# 130809_AriloTX_0_0.net
KiCad netlist of a schematic drawn in EAGLE
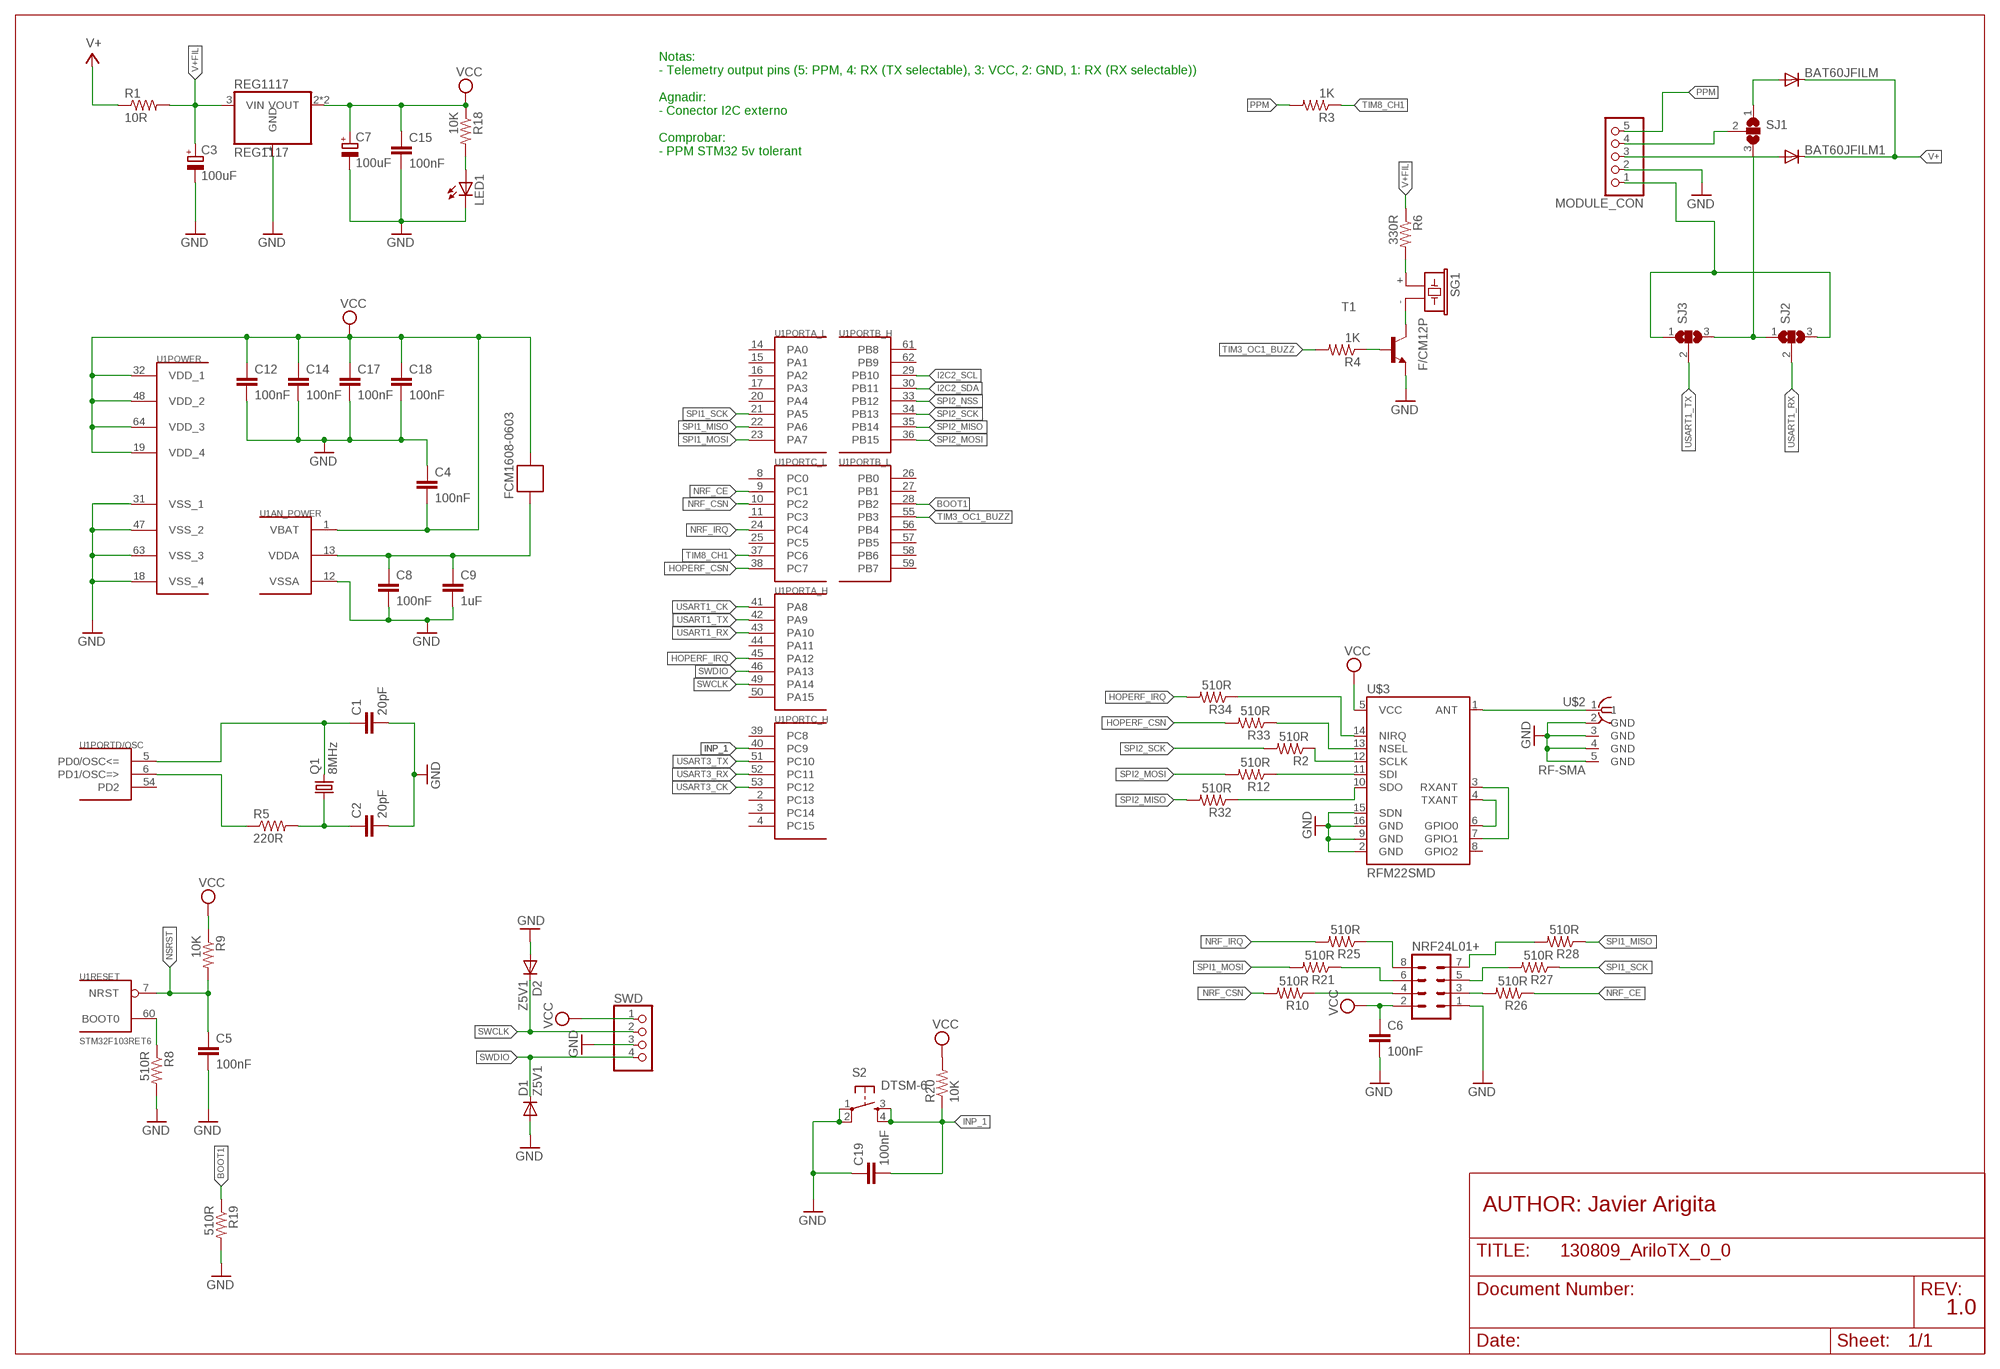
[diagram p0: schematic, sheet 1]

(export (version "E")
  (design (tool "Eeschema 10.0.6"))
  (components
    (comp (ref "BAT60JFILM")
      (value "DIODE-SOD323-R")
      (footprint "eagle-import:SOD323-R")
      (libsource (lib "eagle-import") (part "DIODE-SOD323-R"))
    )
    (comp (ref "BAT60JFILM1")
      (value "DIODE-SOD323-R")
      (footprint "eagle-import:SOD323-R")
      (libsource (lib "eagle-import") (part "DIODE-SOD323-R"))
    )
    (comp (ref "C1")
      (value "20pF")
      (footprint "eagle-import:C0805")
      (libsource (lib "eagle-import") (part "C-EUC0805"))
    )
    (comp (ref "C2")
      (value "20pF")
      (footprint "eagle-import:C0805")
      (libsource (lib "eagle-import") (part "C-EUC0805"))
    )
    (comp (ref "C3")
      (value "100uF")
      (footprint "eagle-import:SMC_B")
      (libsource (lib "eagle-import") (part "CPOL-EUSMCB"))
    )
    (comp (ref "C4")
      (value "100nF")
      (footprint "eagle-import:C0805")
      (libsource (lib "eagle-import") (part "C-EUC0805"))
    )
    (comp (ref "C5")
      (value "100nF")
      (footprint "eagle-import:C0805")
      (libsource (lib "eagle-import") (part "C-EUC0805"))
    )
    (comp (ref "C6")
      (value "100nF")
      (footprint "eagle-import:C0805")
      (libsource (lib "eagle-import") (part "C-EUC0805"))
    )
    (comp (ref "C7")
      (value "100uF")
      (footprint "eagle-import:SMC_B")
      (libsource (lib "eagle-import") (part "CPOL-EUSMCB"))
    )
    (comp (ref "C8")
      (value "100nF")
      (footprint "eagle-import:C0805")
      (libsource (lib "eagle-import") (part "C-EUC0805"))
    )
    (comp (ref "C9")
      (value "1uF")
      (footprint "eagle-import:C3216")
      (libsource (lib "eagle-import") (part "resistor_C-EUC3216"))
    )
    (comp (ref "C12")
      (value "100nF")
      (footprint "eagle-import:C0805")
      (libsource (lib "eagle-import") (part "C-EUC0805"))
    )
    (comp (ref "C14")
      (value "100nF")
      (footprint "eagle-import:C0805")
      (libsource (lib "eagle-import") (part "C-EUC0805"))
    )
    (comp (ref "C15")
      (value "100nF")
      (footprint "eagle-import:C0805")
      (libsource (lib "eagle-import") (part "C-EUC0805"))
    )
    (comp (ref "C17")
      (value "100nF")
      (footprint "eagle-import:C0805")
      (libsource (lib "eagle-import") (part "C-EUC0805"))
    )
    (comp (ref "C18")
      (value "100nF")
      (footprint "eagle-import:C0805")
      (libsource (lib "eagle-import") (part "C-EUC0805"))
    )
    (comp (ref "C19")
      (value "100nF")
      (footprint "eagle-import:C0805")
      (libsource (lib "eagle-import") (part "C-EUC0805"))
    )
    (comp (ref "D1")
      (value "Z5V1")
      (footprint "eagle-import:SOD323-R")
      (libsource (lib "eagle-import") (part "DIODE-SOD323-R"))
    )
    (comp (ref "D2")
      (value "Z5V1")
      (footprint "eagle-import:SOD323-R")
      (libsource (lib "eagle-import") (part "DIODE-SOD323-R"))
    )
    (comp (ref "FCM1608-0603")
      (value "FERRITE-BEAD")
      (footprint "eagle-import:R0603")
      (libsource (lib "eagle-import") (part "FERRITE-BEAD"))
    )
    (comp (ref "LED1")
      (value "LED0805")
      (footprint "eagle-import:CHIPLED_0805")
      (libsource (lib "eagle-import") (part "LED0805"))
    )
    (comp (ref "MODULE_CON")
      (value "PINHD-1X5")
      (footprint "eagle-import:1X05")
      (libsource (lib "eagle-import") (part "PINHD-1X5"))
    )
    (comp (ref "NRF24L01+")
      (value "MA04-2")
      (footprint "eagle-import:MA04-2")
      (libsource (lib "eagle-import") (part "MA04-2"))
    )
    (comp (ref "Q1")
      (value "8MHz")
      (footprint "eagle-import:SM49")
      (libsource (lib "eagle-import") (part "CRYSTALSM49"))
    )
    (comp (ref "R1")
      (value "10R")
      (footprint "eagle-import:R0805")
      (libsource (lib "eagle-import") (part "RESISTOR0805"))
    )
    (comp (ref "R2")
      (value "510R")
      (footprint "eagle-import:R0805")
      (libsource (lib "eagle-import") (part "RESISTOR0805"))
    )
    (comp (ref "R3")
      (value "1K")
      (footprint "eagle-import:R0805")
      (libsource (lib "eagle-import") (part "RESISTOR0805"))
    )
    (comp (ref "R4")
      (value "1K")
      (footprint "eagle-import:R0805")
      (libsource (lib "eagle-import") (part "RESISTOR0805"))
    )
    (comp (ref "R5")
      (value "220R")
      (footprint "eagle-import:R0805")
      (libsource (lib "eagle-import") (part "RESISTOR0805"))
    )
    (comp (ref "R6")
      (value "330R")
      (footprint "eagle-import:R0805")
      (libsource (lib "eagle-import") (part "RESISTOR0805"))
    )
    (comp (ref "R8")
      (value "510R")
      (footprint "eagle-import:R0805")
      (libsource (lib "eagle-import") (part "RESISTOR0805"))
    )
    (comp (ref "R9")
      (value "10K")
      (footprint "eagle-import:R0805")
      (libsource (lib "eagle-import") (part "RESISTOR0805"))
    )
    (comp (ref "R10")
      (value "510R")
      (footprint "eagle-import:R0805")
      (libsource (lib "eagle-import") (part "RESISTOR0805"))
    )
    (comp (ref "R12")
      (value "510R")
      (footprint "eagle-import:R0805")
      (libsource (lib "eagle-import") (part "RESISTOR0805"))
    )
    (comp (ref "R18")
      (value "10K")
      (footprint "eagle-import:R0805")
      (libsource (lib "eagle-import") (part "RESISTOR0805"))
    )
    (comp (ref "R19")
      (value "510R")
      (footprint "eagle-import:R0805")
      (libsource (lib "eagle-import") (part "RESISTOR0805"))
    )
    (comp (ref "R20")
      (value "10K")
      (footprint "eagle-import:R0805")
      (libsource (lib "eagle-import") (part "RESISTOR0805"))
    )
    (comp (ref "R21")
      (value "510R")
      (footprint "eagle-import:R0805")
      (libsource (lib "eagle-import") (part "RESISTOR0805"))
    )
    (comp (ref "R25")
      (value "510R")
      (footprint "eagle-import:R0805")
      (libsource (lib "eagle-import") (part "RESISTOR0805"))
    )
    (comp (ref "R26")
      (value "510R")
      (footprint "eagle-import:R0805")
      (libsource (lib "eagle-import") (part "RESISTOR0805"))
    )
    (comp (ref "R27")
      (value "510R")
      (footprint "eagle-import:R0805")
      (libsource (lib "eagle-import") (part "RESISTOR0805"))
    )
    (comp (ref "R28")
      (value "510R")
      (footprint "eagle-import:R0805")
      (libsource (lib "eagle-import") (part "RESISTOR0805"))
    )
    (comp (ref "R32")
      (value "510R")
      (footprint "eagle-import:R0805")
      (libsource (lib "eagle-import") (part "RESISTOR0805"))
    )
    (comp (ref "R33")
      (value "510R")
      (footprint "eagle-import:R0805")
      (libsource (lib "eagle-import") (part "RESISTOR0805"))
    )
    (comp (ref "R34")
      (value "510R")
      (footprint "eagle-import:R0805")
      (libsource (lib "eagle-import") (part "RESISTOR0805"))
    )
    (comp (ref "REG1117")
      (value "REG1117")
      (footprint "eagle-import:SOT223")
      (libsource (lib "eagle-import") (part "REG1117"))
    )
    (comp (ref "S2")
      (value "DTSM-6")
      (footprint "eagle-import:DTSM-6")
      (libsource (lib "eagle-import") (part "DTSM-6"))
    )
    (comp (ref "SG1")
      (value "F/CM12P")
      (footprint "eagle-import:F_CM12P")
      (libsource (lib "eagle-import") (part "F/CM12P"))
    )
    (comp (ref "SJ1")
      (value "SJ2W")
      (footprint "eagle-import:SJ_2")
      (libsource (lib "eagle-import") (part "SJ2W"))
    )
    (comp (ref "SJ2")
      (value "SJ2W")
      (footprint "eagle-import:SJ_2")
      (libsource (lib "eagle-import") (part "SJ2W"))
    )
    (comp (ref "SJ3")
      (value "SJ2W")
      (footprint "eagle-import:SJ_2")
      (libsource (lib "eagle-import") (part "SJ2W"))
    )
    (comp (ref "SWD")
      (value "PINHD-1X4")
      (footprint "eagle-import:1X04")
      (libsource (lib "eagle-import") (part "PINHD-1X4"))
    )
    (comp (ref "T1")
      (value "BC848-NPN-SOT23-BEC")
      (footprint "eagle-import:SOT23-BEC")
      (libsource (lib "eagle-import") (part "-NPN-SOT23-BECBC848"))
    )
    (comp (ref "U$2")
      (value "RF-SMA")
      (footprint "eagle-import:BU-SMA-H")
      (libsource (lib "eagle-import") (part "RF-SMA"))
    )
    (comp (ref "U$3")
      (value "RFM22SMD")
      (footprint "eagle-import:RFM22-XXX-S2")
      (libsource (lib "eagle-import") (part "RFM22SMD"))
    )
    (comp (ref "U1")
      (value "STM32F103RET6")
      (footprint "eagle-import:TQFP64")
      (libsource (lib "eagle-import") (part "STM32F10XRXT6"))
    )
  )
  (nets
    (net (code "1") (name "BOOT1") (class "Default")
      (node (ref "R19") (pin "1") (pinfunction "1_1") (pintype "passive"))
      (node (ref "U1") (pin "28") (pinfunction "PB2_28") (pintype "bidirectional"))
    )
    (net (code "2") (name "GND") (class "Default")
      (node (ref "C1") (pin "2") (pinfunction "2_2") (pintype "passive"))
      (node (ref "C12") (pin "2") (pinfunction "2_2") (pintype "passive"))
      (node (ref "C14") (pin "2") (pinfunction "2_2") (pintype "passive"))
      (node (ref "C15") (pin "2") (pinfunction "2_2") (pintype "passive"))
      (node (ref "C17") (pin "2") (pinfunction "2_2") (pintype "passive"))
      (node (ref "C18") (pin "2") (pinfunction "2_2") (pintype "passive"))
      (node (ref "C19") (pin "1") (pinfunction "1_1") (pintype "passive"))
      (node (ref "C2") (pin "2") (pinfunction "2_2") (pintype "passive"))
      (node (ref "C3") (pin "-") (pinfunction "-_-") (pintype "passive"))
      (node (ref "C4") (pin "1") (pinfunction "1_1") (pintype "passive"))
      (node (ref "C5") (pin "2") (pinfunction "2_2") (pintype "passive"))
      (node (ref "C6") (pin "2") (pinfunction "2_2") (pintype "passive"))
      (node (ref "C7") (pin "-") (pinfunction "-_-") (pintype "passive"))
      (node (ref "C8") (pin "2") (pinfunction "2_2") (pintype "passive"))
      (node (ref "C9") (pin "2") (pinfunction "2_2") (pintype "passive"))
      (node (ref "D1") (pin "A") (pinfunction "A_A") (pintype "passive"))
      (node (ref "D2") (pin "A") (pinfunction "A_A") (pintype "passive"))
      (node (ref "LED1") (pin "C") (pinfunction "C_C") (pintype "passive"))
      (node (ref "MODULE_CON") (pin "2") (pinfunction "2_2") (pintype "passive"))
      (node (ref "NRF24L01+") (pin "1") (pinfunction "1_1") (pintype "passive"))
      (node (ref "R19") (pin "2") (pinfunction "2_2") (pintype "passive"))
      (node (ref "R8") (pin "2") (pinfunction "2_2") (pintype "passive"))
      (node (ref "REG1117") (pin "1") (pinfunction "GND_1") (pintype "power_in"))
      (node (ref "S2") (pin "1") (pinfunction "1_1") (pintype "passive"))
      (node (ref "S2") (pin "2") (pinfunction "2_2") (pintype "passive"))
      (node (ref "SWD") (pin "3") (pinfunction "3_3") (pintype "passive"))
      (node (ref "T1") (pin "E") (pinfunction "E_E") (pintype "passive"))
      (node (ref "U$2") (pin "2") (pinfunction "GND_2") (pintype "power_in"))
      (node (ref "U$2") (pin "3") (pinfunction "GND_3") (pintype "bidirectional"))
      (node (ref "U$2") (pin "4") (pinfunction "GND_4") (pintype "bidirectional"))
      (node (ref "U$2") (pin "5") (pinfunction "GND_5") (pintype "bidirectional"))
      (node (ref "U$3") (pin "15") (pinfunction "SDN_15") (pintype "input"))
      (node (ref "U$3") (pin "16") (pinfunction "GND_16") (pintype "power_in"))
      (node (ref "U$3") (pin "2") (pinfunction "GND_2") (pintype "power_in"))
      (node (ref "U$3") (pin "9") (pinfunction "GND_9") (pintype "power_in"))
      (node (ref "U1") (pin "12") (pinfunction "VSSA_12") (pintype "power_in"))
      (node (ref "U1") (pin "18") (pinfunction "VSS_4_18") (pintype "power_in"))
      (node (ref "U1") (pin "31") (pinfunction "VSS_1_31") (pintype "power_in"))
      (node (ref "U1") (pin "47") (pinfunction "VSS_2_47") (pintype "power_in"))
      (node (ref "U1") (pin "63") (pinfunction "VSS_3_63") (pintype "power_in"))
    )
    (net (code "3") (name "HOPERF_CSN") (class "Default")
      (node (ref "R33") (pin "2") (pinfunction "2_2") (pintype "passive"))
      (node (ref "U1") (pin "38") (pinfunction "PC7_38") (pintype "bidirectional"))
    )
    (net (code "4") (name "HOPERF_IRQ") (class "Default")
      (node (ref "R34") (pin "2") (pinfunction "2_2") (pintype "passive"))
      (node (ref "U1") (pin "45") (pinfunction "PA12_45") (pintype "bidirectional"))
    )
    (net (code "5") (name "I2C2_SCL") (class "Default")
      (node (ref "U1") (pin "29") (pinfunction "PB10_29") (pintype "bidirectional"))
    )
    (net (code "6") (name "I2C2_SDA") (class "Default")
      (node (ref "U1") (pin "30") (pinfunction "PB11_30") (pintype "bidirectional"))
    )
    (net (code "7") (name "INP_1") (class "Default")
      (node (ref "C19") (pin "2") (pinfunction "2_2") (pintype "passive"))
      (node (ref "R20") (pin "1") (pinfunction "1_1") (pintype "passive"))
      (node (ref "S2") (pin "3") (pinfunction "3_3") (pintype "passive"))
      (node (ref "S2") (pin "4") (pinfunction "4_4") (pintype "passive"))
      (node (ref "U1") (pin "40") (pinfunction "PC9_40") (pintype "bidirectional"))
    )
    (net (code "8") (name "NRF_CE") (class "Default")
      (node (ref "R26") (pin "1") (pinfunction "1_1") (pintype "passive"))
      (node (ref "U1") (pin "9") (pinfunction "PC1_9") (pintype "bidirectional"))
    )
    (net (code "9") (name "NRF_CSN") (class "Default")
      (node (ref "R10") (pin "2") (pinfunction "2_2") (pintype "passive"))
      (node (ref "U1") (pin "10") (pinfunction "PC2_10") (pintype "bidirectional"))
    )
    (net (code "10") (name "NRF_IRQ") (class "Default")
      (node (ref "R25") (pin "2") (pinfunction "2_2") (pintype "passive"))
      (node (ref "U1") (pin "24") (pinfunction "PC4_24") (pintype "bidirectional"))
    )
    (net (code "11") (name "NSRST") (class "Default")
      (node (ref "C5") (pin "1") (pinfunction "1_1") (pintype "passive"))
      (node (ref "R9") (pin "2") (pinfunction "2_2") (pintype "passive"))
      (node (ref "U1") (pin "7") (pinfunction "NRST_7") (pintype "input"))
    )
    (net (code "12") (name "Net-(BAT60JFILM-PadA)") (class "Default")
      (node (ref "BAT60JFILM") (pin "A") (pinfunction "A_A") (pintype "passive"))
      (node (ref "SJ1") (pin "1") (pinfunction "1_1") (pintype "passive"))
    )
    (net (code "13") (name "Net-(BAT60JFILM1-PadA)") (class "Default")
      (node (ref "BAT60JFILM1") (pin "A") (pinfunction "A_A") (pintype "passive"))
      (node (ref "MODULE_CON") (pin "3") (pinfunction "3_3") (pintype "passive"))
    )
    (net (code "14") (name "Net-(C2-Pad1)") (class "Default")
      (node (ref "C2") (pin "1") (pinfunction "1_1") (pintype "passive"))
      (node (ref "Q1") (pin "1") (pinfunction "1_1") (pintype "passive"))
      (node (ref "R5") (pin "2") (pinfunction "2_2") (pintype "passive"))
    )
    (net (code "15") (name "Net-(FCM1608-0603-P$2)") (class "Default")
      (node (ref "C8") (pin "1") (pinfunction "1_1") (pintype "passive"))
      (node (ref "C9") (pin "1") (pinfunction "1_1") (pintype "passive"))
      (node (ref "FCM1608-0603") (pin "2") (pinfunction "P$2_2") (pintype "bidirectional"))
      (node (ref "U1") (pin "13") (pinfunction "VDDA_13") (pintype "power_in"))
    )
    (net (code "16") (name "Net-(LED1-PadA)") (class "Default")
      (node (ref "LED1") (pin "A") (pinfunction "A_A") (pintype "passive"))
      (node (ref "R18") (pin "2") (pinfunction "2_2") (pintype "passive"))
    )
    (net (code "17") (name "Net-(MODULE_CON-Pad1)") (class "Default")
      (node (ref "MODULE_CON") (pin "1") (pinfunction "1_1") (pintype "passive"))
      (node (ref "SJ2") (pin "3") (pinfunction "3_3") (pintype "passive"))
      (node (ref "SJ3") (pin "1") (pinfunction "1_1") (pintype "passive"))
    )
    (net (code "18") (name "Net-(MODULE_CON-Pad4)") (class "Default")
      (node (ref "MODULE_CON") (pin "4") (pinfunction "4_4") (pintype "passive"))
      (node (ref "SJ1") (pin "2") (pinfunction "2_2") (pintype "passive"))
    )
    (net (code "19") (name "Net-(NRF24L01+-Pad3)") (class "Default")
      (node (ref "NRF24L01+") (pin "3") (pinfunction "3_3") (pintype "passive"))
      (node (ref "R26") (pin "2") (pinfunction "2_2") (pintype "passive"))
    )
    (net (code "20") (name "Net-(NRF24L01+-Pad4)") (class "Default")
      (node (ref "NRF24L01+") (pin "4") (pinfunction "4_4") (pintype "passive"))
      (node (ref "R10") (pin "1") (pinfunction "1_1") (pintype "passive"))
    )
    (net (code "21") (name "Net-(NRF24L01+-Pad5)") (class "Default")
      (node (ref "NRF24L01+") (pin "5") (pinfunction "5_5") (pintype "passive"))
      (node (ref "R27") (pin "2") (pinfunction "2_2") (pintype "passive"))
    )
    (net (code "22") (name "Net-(NRF24L01+-Pad6)") (class "Default")
      (node (ref "NRF24L01+") (pin "6") (pinfunction "6_6") (pintype "passive"))
      (node (ref "R21") (pin "1") (pinfunction "1_1") (pintype "passive"))
    )
    (net (code "23") (name "Net-(NRF24L01+-Pad7)") (class "Default")
      (node (ref "NRF24L01+") (pin "7") (pinfunction "7_7") (pintype "passive"))
      (node (ref "R28") (pin "2") (pinfunction "2_2") (pintype "passive"))
    )
    (net (code "24") (name "Net-(NRF24L01+-Pad8)") (class "Default")
      (node (ref "NRF24L01+") (pin "8") (pinfunction "8_8") (pintype "passive"))
      (node (ref "R25") (pin "1") (pinfunction "1_1") (pintype "passive"))
    )
    (net (code "25") (name "Net-(R4-Pad1)") (class "Default")
      (node (ref "R4") (pin "1") (pinfunction "1_1") (pintype "passive"))
      (node (ref "T1") (pin "B") (pinfunction "B_B") (pintype "passive"))
    )
    (net (code "26") (name "Net-(SG1-1)") (class "Default")
      (node (ref "R6") (pin "2") (pinfunction "2_2") (pintype "passive"))
      (node (ref "SG1") (pin "+") (pinfunction "1_+") (pintype "passive"))
    )
    (net (code "27") (name "Net-(SG1-2)") (class "Default")
      (node (ref "SG1") (pin "-") (pinfunction "2_-") (pintype "passive"))
      (node (ref "T1") (pin "C") (pinfunction "C_C") (pintype "passive"))
    )
    (net (code "28") (name "Net-(SJ1-Pad3)") (class "Default")
      (node (ref "SJ1") (pin "3") (pinfunction "3_3") (pintype "passive"))
      (node (ref "SJ2") (pin "1") (pinfunction "1_1") (pintype "passive"))
      (node (ref "SJ3") (pin "3") (pinfunction "3_3") (pintype "passive"))
    )
    (net (code "29") (name "Net-(U$3-ANT)") (class "Default")
      (node (ref "U$2") (pin "1") (pinfunction "1_1") (pintype "passive"))
      (node (ref "U$3") (pin "1") (pinfunction "ANT_1") (pintype "bidirectional"))
    )
    (net (code "30") (name "Net-(U$3-GPIO0)") (class "Default")
      (node (ref "U$3") (pin "4") (pinfunction "TXANT_4") (pintype "input"))
      (node (ref "U$3") (pin "6") (pinfunction "GPIO0_6") (pintype "bidirectional"))
    )
    (net (code "31") (name "Net-(U$3-GPIO1)") (class "Default")
      (node (ref "U$3") (pin "3") (pinfunction "RXANT_3") (pintype "input"))
      (node (ref "U$3") (pin "7") (pinfunction "GPIO1_7") (pintype "bidirectional"))
    )
    (net (code "32") (name "Net-(U$3-NIRQ)") (class "Default")
      (node (ref "R34") (pin "1") (pinfunction "1_1") (pintype "passive"))
      (node (ref "U$3") (pin "14") (pinfunction "NIRQ_14") (pintype "output"))
    )
    (net (code "33") (name "Net-(U$3-NSEL)") (class "Default")
      (node (ref "R33") (pin "1") (pinfunction "1_1") (pintype "passive"))
      (node (ref "U$3") (pin "13") (pinfunction "NSEL_13") (pintype "input"))
    )
    (net (code "34") (name "Net-(U$3-SCLK)") (class "Default")
      (node (ref "R2") (pin "1") (pinfunction "1_1") (pintype "passive"))
      (node (ref "U$3") (pin "12") (pinfunction "SCLK_12") (pintype "input"))
    )
    (net (code "35") (name "Net-(U$3-SDI)") (class "Default")
      (node (ref "R12") (pin "1") (pinfunction "1_1") (pintype "passive"))
      (node (ref "U$3") (pin "11") (pinfunction "SDI_11") (pintype "input"))
    )
    (net (code "36") (name "Net-(U$3-SDO)") (class "Default")
      (node (ref "R32") (pin "1") (pinfunction "1_1") (pintype "passive"))
      (node (ref "U$3") (pin "10") (pinfunction "SDO_10") (pintype "output"))
    )
    (net (code "37") (name "Net-(U1H-PD0{slash}OSC<=)") (class "Default")
      (node (ref "C1") (pin "1") (pinfunction "1_1") (pintype "passive"))
      (node (ref "Q1") (pin "2") (pinfunction "2_2") (pintype "passive"))
      (node (ref "U1") (pin "5") (pinfunction "PD0/OSC<=_5") (pintype "bidirectional"))
    )
    (net (code "38") (name "Net-(U1H-PD1{slash}OSC=>)") (class "Default")
      (node (ref "R5") (pin "1") (pinfunction "1_1") (pintype "passive"))
      (node (ref "U1") (pin "6") (pinfunction "PD1/OSC=>_6") (pintype "bidirectional"))
    )
    (net (code "39") (name "Net-(U1J-BOOT0)") (class "Default")
      (node (ref "R8") (pin "1") (pinfunction "1_1") (pintype "passive"))
      (node (ref "U1") (pin "60") (pinfunction "BOOT0_60") (pintype "input"))
    )
    (net (code "40") (name "PPM") (class "Default")
      (node (ref "MODULE_CON") (pin "5") (pinfunction "5_5") (pintype "passive"))
      (node (ref "R3") (pin "2") (pinfunction "2_2") (pintype "passive"))
    )
    (net (code "41") (name "SPI1_MISO") (class "Default")
      (node (ref "R28") (pin "1") (pinfunction "1_1") (pintype "passive"))
      (node (ref "U1") (pin "22") (pinfunction "PA6_22") (pintype "bidirectional"))
    )
    (net (code "42") (name "SPI1_MOSI") (class "Default")
      (node (ref "R21") (pin "2") (pinfunction "2_2") (pintype "passive"))
      (node (ref "U1") (pin "23") (pinfunction "PA7_23") (pintype "bidirectional"))
    )
    (net (code "43") (name "SPI1_SCK") (class "Default")
      (node (ref "R27") (pin "1") (pinfunction "1_1") (pintype "passive"))
      (node (ref "U1") (pin "21") (pinfunction "PA5_21") (pintype "bidirectional"))
    )
    (net (code "44") (name "SPI2_MISO") (class "Default")
      (node (ref "R32") (pin "2") (pinfunction "2_2") (pintype "passive"))
      (node (ref "U1") (pin "35") (pinfunction "PB14_35") (pintype "bidirectional"))
    )
    (net (code "45") (name "SPI2_MOSI") (class "Default")
      (node (ref "R12") (pin "2") (pinfunction "2_2") (pintype "passive"))
      (node (ref "U1") (pin "36") (pinfunction "PB15_36") (pintype "bidirectional"))
    )
    (net (code "46") (name "SPI2_NSS") (class "Default")
      (node (ref "U1") (pin "33") (pinfunction "PB12_33") (pintype "bidirectional"))
    )
    (net (code "47") (name "SPI2_SCK") (class "Default")
      (node (ref "R2") (pin "2") (pinfunction "2_2") (pintype "passive"))
      (node (ref "U1") (pin "34") (pinfunction "PB13_34") (pintype "bidirectional"))
    )
    (net (code "48") (name "SWCLK") (class "Default")
      (node (ref "D2") (pin "C") (pinfunction "C_C") (pintype "passive"))
      (node (ref "SWD") (pin "2") (pinfunction "2_2") (pintype "passive"))
      (node (ref "U1") (pin "49") (pinfunction "PA14_49") (pintype "bidirectional"))
    )
    (net (code "49") (name "SWDIO") (class "Default")
      (node (ref "D1") (pin "C") (pinfunction "C_C") (pintype "passive"))
      (node (ref "SWD") (pin "4") (pinfunction "4_4") (pintype "passive"))
      (node (ref "U1") (pin "46") (pinfunction "PA13_46") (pintype "bidirectional"))
    )
    (net (code "50") (name "TIM3_OC1_BUZZ") (class "Default")
      (node (ref "R4") (pin "2") (pinfunction "2_2") (pintype "passive"))
      (node (ref "U1") (pin "55") (pinfunction "PB3_55") (pintype "bidirectional"))
    )
    (net (code "51") (name "TIM8_CH1") (class "Default")
      (node (ref "R3") (pin "1") (pinfunction "1_1") (pintype "passive"))
      (node (ref "U1") (pin "37") (pinfunction "PC6_37") (pintype "bidirectional"))
    )
    (net (code "52") (name "USART1_CK") (class "Default")
      (node (ref "U1") (pin "41") (pinfunction "PA8_41") (pintype "bidirectional"))
    )
    (net (code "53") (name "USART1_RX") (class "Default")
      (node (ref "SJ2") (pin "2") (pinfunction "2_2") (pintype "passive"))
      (node (ref "U1") (pin "43") (pinfunction "PA10_43") (pintype "bidirectional"))
    )
    (net (code "54") (name "USART1_TX") (class "Default")
      (node (ref "SJ3") (pin "2") (pinfunction "2_2") (pintype "passive"))
      (node (ref "U1") (pin "42") (pinfunction "PA9_42") (pintype "bidirectional"))
    )
    (net (code "55") (name "USART3_CK") (class "Default")
      (node (ref "U1") (pin "53") (pinfunction "PC12_53") (pintype "bidirectional"))
    )
    (net (code "56") (name "USART3_RX") (class "Default")
      (node (ref "U1") (pin "52") (pinfunction "PC11_52") (pintype "bidirectional"))
    )
    (net (code "57") (name "USART3_TX") (class "Default")
      (node (ref "U1") (pin "51") (pinfunction "PC10_51") (pintype "bidirectional"))
    )
    (net (code "58") (name "V+") (class "Default")
      (node (ref "BAT60JFILM") (pin "C") (pinfunction "C_C") (pintype "passive"))
      (node (ref "BAT60JFILM1") (pin "C") (pinfunction "C_C") (pintype "passive"))
      (node (ref "R1") (pin "1") (pinfunction "1_1") (pintype "passive"))
    )
    (net (code "59") (name "V+FIL") (class "Default")
      (node (ref "C3") (pin "+") (pinfunction "+_+") (pintype "passive"))
      (node (ref "R1") (pin "2") (pinfunction "2_2") (pintype "passive"))
      (node (ref "R6") (pin "1") (pinfunction "1_1") (pintype "passive"))
      (node (ref "REG1117") (pin "3") (pinfunction "VIN_3") (pintype "input"))
    )
    (net (code "60") (name "VCC") (class "Default")
      (node (ref "C12") (pin "1") (pinfunction "1_1") (pintype "passive"))
      (node (ref "C14") (pin "1") (pinfunction "1_1") (pintype "passive"))
      (node (ref "C15") (pin "1") (pinfunction "1_1") (pintype "passive"))
      (node (ref "C17") (pin "1") (pinfunction "1_1") (pintype "passive"))
      (node (ref "C18") (pin "1") (pinfunction "1_1") (pintype "passive"))
      (node (ref "C4") (pin "2") (pinfunction "2_2") (pintype "passive"))
      (node (ref "C6") (pin "1") (pinfunction "1_1") (pintype "passive"))
      (node (ref "C7") (pin "+") (pinfunction "+_+") (pintype "passive"))
      (node (ref "FCM1608-0603") (pin "1") (pinfunction "P$1_1") (pintype "bidirectional"))
      (node (ref "NRF24L01+") (pin "2") (pinfunction "2_2") (pintype "passive"))
      (node (ref "R18") (pin "1") (pinfunction "1_1") (pintype "passive"))
      (node (ref "R20") (pin "2") (pinfunction "2_2") (pintype "passive"))
      (node (ref "R9") (pin "1") (pinfunction "1_1") (pintype "passive"))
      (node (ref "REG1117") (pin "2") (pinfunction "VOUT_2") (pintype "power_in"))
      (node (ref "REG1117") (pin "4") (pinfunction "VOUT_4") (pintype "power_in"))
      (node (ref "SWD") (pin "1") (pinfunction "1_1") (pintype "passive"))
      (node (ref "U$3") (pin "5") (pinfunction "VCC_5") (pintype "bidirectional"))
      (node (ref "U1") (pin "1") (pinfunction "VBAT_1") (pintype "power_in"))
      (node (ref "U1") (pin "19") (pinfunction "VDD_4_19") (pintype "power_in"))
      (node (ref "U1") (pin "32") (pinfunction "VDD_1_32") (pintype "power_in"))
      (node (ref "U1") (pin "48") (pinfunction "VDD_2_48") (pintype "power_in"))
      (node (ref "U1") (pin "64") (pinfunction "VDD_3_64") (pintype "power_in"))
    )
    (net (code "61") (name "unconnected-(U$3-GPIO2-Pad8)") (class "Default")
      (node (ref "U$3") (pin "8") (pinfunction "GPIO2_8") (pintype "bidirectional"))
    )
    (net (code "62") (name "unconnected-(U1B-PA11-Pad44)") (class "Default")
      (node (ref "U1") (pin "44") (pinfunction "PA11_44") (pintype "bidirectional"))
    )
    (net (code "63") (name "unconnected-(U1B-PA15-Pad50)") (class "Default")
      (node (ref "U1") (pin "50") (pinfunction "PA15_50") (pintype "bidirectional"))
    )
    (net (code "64") (name "unconnected-(U1C-PA0-Pad14)") (class "Default")
      (node (ref "U1") (pin "14") (pinfunction "PA0_14") (pintype "bidirectional"))
    )
    (net (code "65") (name "unconnected-(U1C-PA1-Pad15)") (class "Default")
      (node (ref "U1") (pin "15") (pinfunction "PA1_15") (pintype "bidirectional"))
    )
    (net (code "66") (name "unconnected-(U1C-PA2-Pad16)") (class "Default")
      (node (ref "U1") (pin "16") (pinfunction "PA2_16") (pintype "bidirectional"))
    )
    (net (code "67") (name "unconnected-(U1C-PA3-Pad17)") (class "Default")
      (node (ref "U1") (pin "17") (pinfunction "PA3_17") (pintype "bidirectional"))
    )
    (net (code "68") (name "unconnected-(U1C-PA4-Pad20)") (class "Default")
      (node (ref "U1") (pin "20") (pinfunction "PA4_20") (pintype "bidirectional"))
    )
    (net (code "69") (name "unconnected-(U1D-PB8-Pad61)") (class "Default")
      (node (ref "U1") (pin "61") (pinfunction "PB8_61") (pintype "bidirectional"))
    )
    (net (code "70") (name "unconnected-(U1D-PB9-Pad62)") (class "Default")
      (node (ref "U1") (pin "62") (pinfunction "PB9_62") (pintype "bidirectional"))
    )
    (net (code "71") (name "unconnected-(U1E-PB0-Pad26)") (class "Default")
      (node (ref "U1") (pin "26") (pinfunction "PB0_26") (pintype "bidirectional"))
    )
    (net (code "72") (name "unconnected-(U1E-PB1-Pad27)") (class "Default")
      (node (ref "U1") (pin "27") (pinfunction "PB1_27") (pintype "bidirectional"))
    )
    (net (code "73") (name "unconnected-(U1E-PB4-Pad56)") (class "Default")
      (node (ref "U1") (pin "56") (pinfunction "PB4_56") (pintype "bidirectional"))
    )
    (net (code "74") (name "unconnected-(U1E-PB5-Pad57)") (class "Default")
      (node (ref "U1") (pin "57") (pinfunction "PB5_57") (pintype "bidirectional"))
    )
    (net (code "75") (name "unconnected-(U1E-PB6-Pad58)") (class "Default")
      (node (ref "U1") (pin "58") (pinfunction "PB6_58") (pintype "bidirectional"))
    )
    (net (code "76") (name "unconnected-(U1E-PB7-Pad59)") (class "Default")
      (node (ref "U1") (pin "59") (pinfunction "PB7_59") (pintype "bidirectional"))
    )
    (net (code "77") (name "unconnected-(U1F-PC8-Pad39)") (class "Default")
      (node (ref "U1") (pin "39") (pinfunction "PC8_39") (pintype "bidirectional"))
    )
    (net (code "78") (name "unconnected-(U1F-PC13-Pad2)") (class "Default")
      (node (ref "U1") (pin "2") (pinfunction "PC13_2") (pintype "bidirectional"))
    )
    (net (code "79") (name "unconnected-(U1F-PC14-Pad3)") (class "Default")
      (node (ref "U1") (pin "3") (pinfunction "PC14_3") (pintype "bidirectional"))
    )
    (net (code "80") (name "unconnected-(U1F-PC15-Pad4)") (class "Default")
      (node (ref "U1") (pin "4") (pinfunction "PC15_4") (pintype "bidirectional"))
    )
    (net (code "81") (name "unconnected-(U1G-PC0-Pad8)") (class "Default")
      (node (ref "U1") (pin "8") (pinfunction "PC0_8") (pintype "bidirectional"))
    )
    (net (code "82") (name "unconnected-(U1G-PC3-Pad11)") (class "Default")
      (node (ref "U1") (pin "11") (pinfunction "PC3_11") (pintype "bidirectional"))
    )
    (net (code "83") (name "unconnected-(U1G-PC5-Pad25)") (class "Default")
      (node (ref "U1") (pin "25") (pinfunction "PC5_25") (pintype "bidirectional"))
    )
    (net (code "84") (name "unconnected-(U1H-PD2-Pad54)") (class "Default")
      (node (ref "U1") (pin "54") (pinfunction "PD2_54") (pintype "bidirectional"))
    )
  )
)
